# ESP32_Relay_Card_Relay.net
KiCad netlist of a schematic drawn in Altium Designer
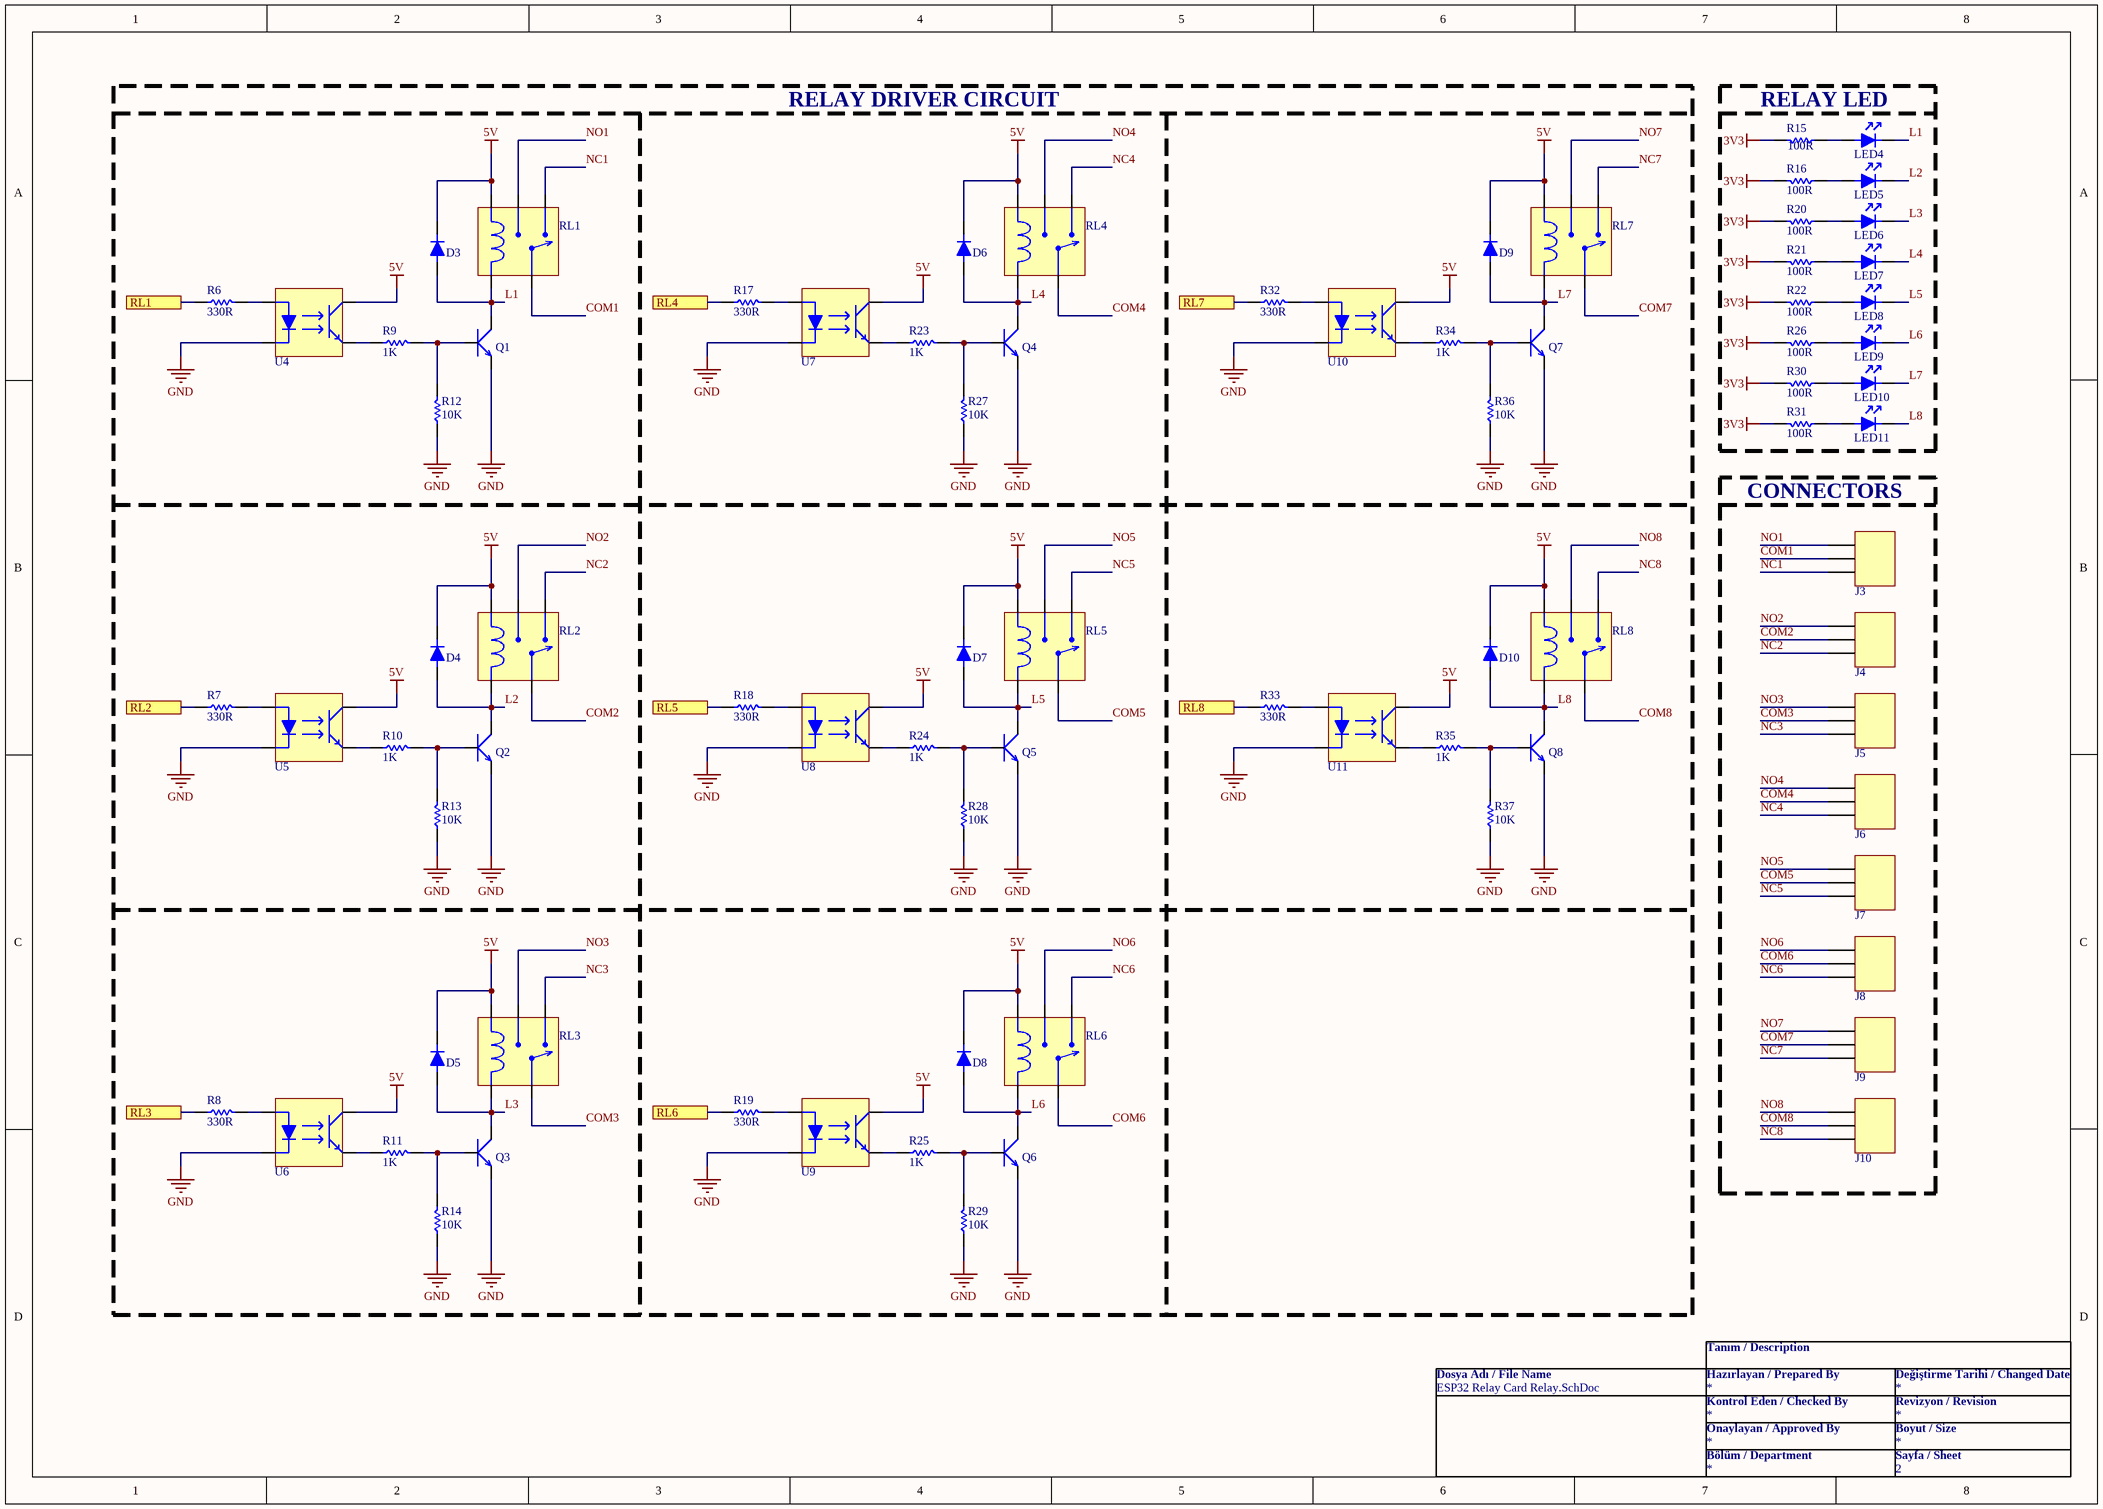
[diagram p0: ESP32 Relay Card Relay.SchDoc]

(export (version "E")
  (design (tool "Eeschema 10.0.6"))
  (components
    (comp (ref "D3")
      (value "1N5819W")
      (footprint "SOD-123F")
      (description "DIODE SCHOTTKY 40V 1A SOD-123F")
      (libsource (lib "ESP32 Relay Card") (part "SCHOTTKY DIODE SMD"))
    )
    (comp (ref "D4")
      (value "1N5819W")
      (footprint "SOD-123F")
      (description "DIODE SCHOTTKY 40V 1A SOD-123F")
      (libsource (lib "ESP32 Relay Card") (part "SCHOTTKY DIODE SMD"))
    )
    (comp (ref "D5")
      (value "1N5819W")
      (footprint "SOD-123F")
      (description "DIODE SCHOTTKY 40V 1A SOD-123F")
      (libsource (lib "ESP32 Relay Card") (part "SCHOTTKY DIODE SMD"))
    )
    (comp (ref "D6")
      (value "1N5819W")
      (footprint "SOD-123F")
      (description "DIODE SCHOTTKY 40V 1A SOD-123F")
      (libsource (lib "ESP32 Relay Card") (part "SCHOTTKY DIODE SMD"))
    )
    (comp (ref "D7")
      (value "1N5819W")
      (footprint "SOD-123F")
      (description "DIODE SCHOTTKY 40V 1A SOD-123F")
      (libsource (lib "ESP32 Relay Card") (part "SCHOTTKY DIODE SMD"))
    )
    (comp (ref "D8")
      (value "1N5819W")
      (footprint "SOD-123F")
      (description "DIODE SCHOTTKY 40V 1A SOD-123F")
      (libsource (lib "ESP32 Relay Card") (part "SCHOTTKY DIODE SMD"))
    )
    (comp (ref "D9")
      (value "1N5819W")
      (footprint "SOD-123F")
      (description "DIODE SCHOTTKY 40V 1A SOD-123F")
      (libsource (lib "ESP32 Relay Card") (part "SCHOTTKY DIODE SMD"))
    )
    (comp (ref "D10")
      (value "1N5819W")
      (footprint "SOD-123F")
      (description "DIODE SCHOTTKY 40V 1A SOD-123F")
      (libsource (lib "ESP32 Relay Card") (part "SCHOTTKY DIODE SMD"))
    )
    (comp (ref "J3")
      (value "OSTTA034163")
      (footprint "3POS CONNECTOR")
      (description "TERM BLK 3P 5.08MM PCB")
      (libsource (lib "ESP32 Relay Card") (part "3POS CONNECTOR"))
    )
    (comp (ref "J4")
      (value "OSTTA034163")
      (footprint "3POS CONNECTOR")
      (description "TERM BLK 3P 5.08MM PCB")
      (libsource (lib "ESP32 Relay Card") (part "3POS CONNECTOR"))
    )
    (comp (ref "J5")
      (value "OSTTA034163")
      (footprint "3POS CONNECTOR")
      (description "TERM BLK 3P 5.08MM PCB")
      (libsource (lib "ESP32 Relay Card") (part "3POS CONNECTOR"))
    )
    (comp (ref "J6")
      (value "OSTTA034163")
      (footprint "3POS CONNECTOR")
      (description "TERM BLK 3P 5.08MM PCB")
      (libsource (lib "ESP32 Relay Card") (part "3POS CONNECTOR"))
    )
    (comp (ref "J7")
      (value "OSTTA034163")
      (footprint "3POS CONNECTOR")
      (description "TERM BLK 3P 5.08MM PCB")
      (libsource (lib "ESP32 Relay Card") (part "3POS CONNECTOR"))
    )
    (comp (ref "J8")
      (value "OSTTA034163")
      (footprint "3POS CONNECTOR")
      (description "TERM BLK 3P 5.08MM PCB")
      (libsource (lib "ESP32 Relay Card") (part "3POS CONNECTOR"))
    )
    (comp (ref "J9")
      (value "OSTTA034163")
      (footprint "3POS CONNECTOR")
      (description "TERM BLK 3P 5.08MM PCB")
      (libsource (lib "ESP32 Relay Card") (part "3POS CONNECTOR"))
    )
    (comp (ref "J10")
      (value "OSTTA034163")
      (footprint "3POS CONNECTOR")
      (description "TERM BLK 3P 5.08MM PCB")
      (libsource (lib "ESP32 Relay Card") (part "3POS CONNECTOR"))
    )
    (comp (ref "LED4")
      (value "150080VS75000")
      (footprint "LED 0805 SMD")
      (description "LED GREEN 0805 SMD")
      (libsource (lib "ESP32 Relay Card") (part "GREEN LED 0805 SMD"))
    )
    (comp (ref "LED5")
      (value "150080VS75000")
      (footprint "LED 0805 SMD")
      (description "LED GREEN 0805 SMD")
      (libsource (lib "ESP32 Relay Card") (part "GREEN LED 0805 SMD"))
    )
    (comp (ref "LED6")
      (value "150080VS75000")
      (footprint "LED 0805 SMD")
      (description "LED GREEN 0805 SMD")
      (libsource (lib "ESP32 Relay Card") (part "GREEN LED 0805 SMD"))
    )
    (comp (ref "LED7")
      (value "150080VS75000")
      (footprint "LED 0805 SMD")
      (description "LED GREEN 0805 SMD")
      (libsource (lib "ESP32 Relay Card") (part "GREEN LED 0805 SMD"))
    )
    (comp (ref "LED8")
      (value "150080VS75000")
      (footprint "LED 0805 SMD")
      (description "LED GREEN 0805 SMD")
      (libsource (lib "ESP32 Relay Card") (part "GREEN LED 0805 SMD"))
    )
    (comp (ref "LED9")
      (value "150080VS75000")
      (footprint "LED 0805 SMD")
      (description "LED GREEN 0805 SMD")
      (libsource (lib "ESP32 Relay Card") (part "GREEN LED 0805 SMD"))
    )
    (comp (ref "LED10")
      (value "150080VS75000")
      (footprint "LED 0805 SMD")
      (description "LED GREEN 0805 SMD")
      (libsource (lib "ESP32 Relay Card") (part "GREEN LED 0805 SMD"))
    )
    (comp (ref "LED11")
      (value "150080VS75000")
      (footprint "LED 0805 SMD")
      (description "LED GREEN 0805 SMD")
      (libsource (lib "ESP32 Relay Card") (part "GREEN LED 0805 SMD"))
    )
    (comp (ref "Q1")
      (value "MMBT3904-7-F")
      (footprint "SOT23-3")
      (description "TRANS NPN 40V 0.2A SOT23-3")
      (libsource (lib "ESP32 Relay Card") (part "NPN TRANSISTOR SMD"))
    )
    (comp (ref "Q2")
      (value "MMBT3904-7-F")
      (footprint "SOT23-3")
      (description "TRANS NPN 40V 0.2A SOT23-3")
      (libsource (lib "ESP32 Relay Card") (part "NPN TRANSISTOR SMD"))
    )
    (comp (ref "Q3")
      (value "MMBT3904-7-F")
      (footprint "SOT23-3")
      (description "TRANS NPN 40V 0.2A SOT23-3")
      (libsource (lib "ESP32 Relay Card") (part "NPN TRANSISTOR SMD"))
    )
    (comp (ref "Q4")
      (value "MMBT3904-7-F")
      (footprint "SOT23-3")
      (description "TRANS NPN 40V 0.2A SOT23-3")
      (libsource (lib "ESP32 Relay Card") (part "NPN TRANSISTOR SMD"))
    )
    (comp (ref "Q5")
      (value "MMBT3904-7-F")
      (footprint "SOT23-3")
      (description "TRANS NPN 40V 0.2A SOT23-3")
      (libsource (lib "ESP32 Relay Card") (part "NPN TRANSISTOR SMD"))
    )
    (comp (ref "Q6")
      (value "MMBT3904-7-F")
      (footprint "SOT23-3")
      (description "TRANS NPN 40V 0.2A SOT23-3")
      (libsource (lib "ESP32 Relay Card") (part "NPN TRANSISTOR SMD"))
    )
    (comp (ref "Q7")
      (value "MMBT3904-7-F")
      (footprint "SOT23-3")
      (description "TRANS NPN 40V 0.2A SOT23-3")
      (libsource (lib "ESP32 Relay Card") (part "NPN TRANSISTOR SMD"))
    )
    (comp (ref "Q8")
      (value "MMBT3904-7-F")
      (footprint "SOT23-3")
      (description "TRANS NPN 40V 0.2A SOT23-3")
      (libsource (lib "ESP32 Relay Card") (part "NPN TRANSISTOR SMD"))
    )
    (comp (ref "R6")
      (value "330R")
      (footprint "RES 0603")
      (description "RES 330 OHM 1% 1/5W 0603")
      (fields (field (name "Comment") "CRGH0603F330R"))
      (libsource (lib "ESP32 Relay Card") (part "RES 330 OHM 0603 SMD"))
    )
    (comp (ref "R7")
      (value "330R")
      (footprint "RES 0603")
      (description "RES 330 OHM 1% 1/5W 0603")
      (fields (field (name "Comment") "CRGH0603F330R"))
      (libsource (lib "ESP32 Relay Card") (part "RES 330 OHM 0603 SMD"))
    )
    (comp (ref "R8")
      (value "330R")
      (footprint "RES 0603")
      (description "RES 330 OHM 1% 1/5W 0603")
      (fields (field (name "Comment") "CRGH0603F330R"))
      (libsource (lib "ESP32 Relay Card") (part "RES 330 OHM 0603 SMD"))
    )
    (comp (ref "R9")
      (value "1K")
      (footprint "RES 0603")
      (description "RES 1K OHM 5% 1/5W 0603")
      (fields (field (name "Comment") "CRGH0603J1K0"))
      (libsource (lib "ESP32 Relay Card") (part "RES 1K OHM 0603 SMD"))
    )
    (comp (ref "R10")
      (value "1K")
      (footprint "RES 0603")
      (description "RES 1K OHM 5% 1/5W 0603")
      (fields (field (name "Comment") "CRGH0603J1K0"))
      (libsource (lib "ESP32 Relay Card") (part "RES 1K OHM 0603 SMD"))
    )
    (comp (ref "R11")
      (value "1K")
      (footprint "RES 0603")
      (description "RES 1K OHM 5% 1/5W 0603")
      (fields (field (name "Comment") "CRGH0603J1K0"))
      (libsource (lib "ESP32 Relay Card") (part "RES 1K OHM 0603 SMD"))
    )
    (comp (ref "R12")
      (value "10K")
      (footprint "RES 0603")
      (description "RES 10K OHM 5% 1/5W 0603")
      (fields (field (name "Comment") "CRGH0603J10K"))
      (libsource (lib "ESP32 Relay Card") (part "RES 10K OHM 0603 SMD"))
    )
    (comp (ref "R13")
      (value "10K")
      (footprint "RES 0603")
      (description "RES 10K OHM 5% 1/5W 0603")
      (fields (field (name "Comment") "CRGH0603J10K"))
      (libsource (lib "ESP32 Relay Card") (part "RES 10K OHM 0603 SMD"))
    )
    (comp (ref "R14")
      (value "10K")
      (footprint "RES 0603")
      (description "RES 10K OHM 5% 1/5W 0603")
      (fields (field (name "Comment") "CRGH0603J10K"))
      (libsource (lib "ESP32 Relay Card") (part "RES 10K OHM 0603 SMD"))
    )
    (comp (ref "R15")
      (value "100R")
      (footprint "RES 0603")
      (description "RES 100 OHM 5% 1/5W 0603")
      (fields (field (name "Comment") "CRGH0603J100R"))
      (libsource (lib "ESP32 Relay Card") (part "RES 100 OHM 0603 SMD"))
    )
    (comp (ref "R16")
      (value "100R")
      (footprint "RES 0603")
      (description "RES 100 OHM 5% 1/5W 0603")
      (fields (field (name "Comment") "CRGH0603J100R"))
      (libsource (lib "ESP32 Relay Card") (part "RES 100 OHM 0603 SMD"))
    )
    (comp (ref "R17")
      (value "330R")
      (footprint "RES 0603")
      (description "RES 330 OHM 1% 1/5W 0603")
      (fields (field (name "Comment") "CRGH0603F330R"))
      (libsource (lib "ESP32 Relay Card") (part "RES 330 OHM 0603 SMD"))
    )
    (comp (ref "R18")
      (value "330R")
      (footprint "RES 0603")
      (description "RES 330 OHM 1% 1/5W 0603")
      (fields (field (name "Comment") "CRGH0603F330R"))
      (libsource (lib "ESP32 Relay Card") (part "RES 330 OHM 0603 SMD"))
    )
    (comp (ref "R19")
      (value "330R")
      (footprint "RES 0603")
      (description "RES 330 OHM 1% 1/5W 0603")
      (fields (field (name "Comment") "CRGH0603F330R"))
      (libsource (lib "ESP32 Relay Card") (part "RES 330 OHM 0603 SMD"))
    )
    (comp (ref "R20")
      (value "100R")
      (footprint "RES 0603")
      (description "RES 100 OHM 5% 1/5W 0603")
      (fields (field (name "Comment") "CRGH0603J100R"))
      (libsource (lib "ESP32 Relay Card") (part "RES 100 OHM 0603 SMD"))
    )
    (comp (ref "R21")
      (value "100R")
      (footprint "RES 0603")
      (description "RES 100 OHM 5% 1/5W 0603")
      (fields (field (name "Comment") "CRGH0603J100R"))
      (libsource (lib "ESP32 Relay Card") (part "RES 100 OHM 0603 SMD"))
    )
    (comp (ref "R22")
      (value "100R")
      (footprint "RES 0603")
      (description "RES 100 OHM 5% 1/5W 0603")
      (fields (field (name "Comment") "CRGH0603J100R"))
      (libsource (lib "ESP32 Relay Card") (part "RES 100 OHM 0603 SMD"))
    )
    (comp (ref "R23")
      (value "1K")
      (footprint "RES 0603")
      (description "RES 1K OHM 5% 1/5W 0603")
      (fields (field (name "Comment") "CRGH0603J1K0"))
      (libsource (lib "ESP32 Relay Card") (part "RES 1K OHM 0603 SMD"))
    )
    (comp (ref "R24")
      (value "1K")
      (footprint "RES 0603")
      (description "RES 1K OHM 5% 1/5W 0603")
      (fields (field (name "Comment") "CRGH0603J1K0"))
      (libsource (lib "ESP32 Relay Card") (part "RES 1K OHM 0603 SMD"))
    )
    (comp (ref "R25")
      (value "1K")
      (footprint "RES 0603")
      (description "RES 1K OHM 5% 1/5W 0603")
      (fields (field (name "Comment") "CRGH0603J1K0"))
      (libsource (lib "ESP32 Relay Card") (part "RES 1K OHM 0603 SMD"))
    )
    (comp (ref "R26")
      (value "100R")
      (footprint "RES 0603")
      (description "RES 100 OHM 5% 1/5W 0603")
      (fields (field (name "Comment") "CRGH0603J100R"))
      (libsource (lib "ESP32 Relay Card") (part "RES 100 OHM 0603 SMD"))
    )
    (comp (ref "R27")
      (value "10K")
      (footprint "RES 0603")
      (description "RES 10K OHM 5% 1/5W 0603")
      (fields (field (name "Comment") "CRGH0603J10K"))
      (libsource (lib "ESP32 Relay Card") (part "RES 10K OHM 0603 SMD"))
    )
    (comp (ref "R28")
      (value "10K")
      (footprint "RES 0603")
      (description "RES 10K OHM 5% 1/5W 0603")
      (fields (field (name "Comment") "CRGH0603J10K"))
      (libsource (lib "ESP32 Relay Card") (part "RES 10K OHM 0603 SMD"))
    )
    (comp (ref "R29")
      (value "10K")
      (footprint "RES 0603")
      (description "RES 10K OHM 5% 1/5W 0603")
      (fields (field (name "Comment") "CRGH0603J10K"))
      (libsource (lib "ESP32 Relay Card") (part "RES 10K OHM 0603 SMD"))
    )
    (comp (ref "R30")
      (value "100R")
      (footprint "RES 0603")
      (description "RES 100 OHM 5% 1/5W 0603")
      (fields (field (name "Comment") "CRGH0603J100R"))
      (libsource (lib "ESP32 Relay Card") (part "RES 100 OHM 0603 SMD"))
    )
    (comp (ref "R31")
      (value "100R")
      (footprint "RES 0603")
      (description "RES 100 OHM 5% 1/5W 0603")
      (fields (field (name "Comment") "CRGH0603J100R"))
      (libsource (lib "ESP32 Relay Card") (part "RES 100 OHM 0603 SMD"))
    )
    (comp (ref "R32")
      (value "330R")
      (footprint "RES 0603")
      (description "RES 330 OHM 1% 1/5W 0603")
      (fields (field (name "Comment") "CRGH0603F330R"))
      (libsource (lib "ESP32 Relay Card") (part "RES 330 OHM 0603 SMD"))
    )
    (comp (ref "R33")
      (value "330R")
      (footprint "RES 0603")
      (description "RES 330 OHM 1% 1/5W 0603")
      (fields (field (name "Comment") "CRGH0603F330R"))
      (libsource (lib "ESP32 Relay Card") (part "RES 330 OHM 0603 SMD"))
    )
    (comp (ref "R34")
      (value "1K")
      (footprint "RES 0603")
      (description "RES 1K OHM 5% 1/5W 0603")
      (fields (field (name "Comment") "CRGH0603J1K0"))
      (libsource (lib "ESP32 Relay Card") (part "RES 1K OHM 0603 SMD"))
    )
    (comp (ref "R35")
      (value "1K")
      (footprint "RES 0603")
      (description "RES 1K OHM 5% 1/5W 0603")
      (fields (field (name "Comment") "CRGH0603J1K0"))
      (libsource (lib "ESP32 Relay Card") (part "RES 1K OHM 0603 SMD"))
    )
    (comp (ref "R36")
      (value "10K")
      (footprint "RES 0603")
      (description "RES 10K OHM 5% 1/5W 0603")
      (fields (field (name "Comment") "CRGH0603J10K"))
      (libsource (lib "ESP32 Relay Card") (part "RES 10K OHM 0603 SMD"))
    )
    (comp (ref "R37")
      (value "10K")
      (footprint "RES 0603")
      (description "RES 10K OHM 5% 1/5W 0603")
      (fields (field (name "Comment") "CRGH0603J10K"))
      (libsource (lib "ESP32 Relay Card") (part "RES 10K OHM 0603 SMD"))
    )
    (comp (ref "RL1")
      (value "G5LE-1 DC5")
      (footprint "RELAY")
      (description "RELAY 5VDC COIL 10A")
      (libsource (lib "ESP32 Relay Card") (part "RELAY TH"))
    )
    (comp (ref "RL2")
      (value "G5LE-1 DC5")
      (footprint "RELAY")
      (description "RELAY 5VDC COIL 10A")
      (libsource (lib "ESP32 Relay Card") (part "RELAY TH"))
    )
    (comp (ref "RL3")
      (value "G5LE-1 DC5")
      (footprint "RELAY")
      (description "RELAY 5VDC COIL 10A")
      (libsource (lib "ESP32 Relay Card") (part "RELAY TH"))
    )
    (comp (ref "RL4")
      (value "G5LE-1 DC5")
      (footprint "RELAY")
      (description "RELAY 5VDC COIL 10A")
      (libsource (lib "ESP32 Relay Card") (part "RELAY TH"))
    )
    (comp (ref "RL5")
      (value "G5LE-1 DC5")
      (footprint "RELAY")
      (description "RELAY 5VDC COIL 10A")
      (libsource (lib "ESP32 Relay Card") (part "RELAY TH"))
    )
    (comp (ref "RL6")
      (value "G5LE-1 DC5")
      (footprint "RELAY")
      (description "RELAY 5VDC COIL 10A")
      (libsource (lib "ESP32 Relay Card") (part "RELAY TH"))
    )
    (comp (ref "RL7")
      (value "G5LE-1 DC5")
      (footprint "RELAY")
      (description "RELAY 5VDC COIL 10A")
      (libsource (lib "ESP32 Relay Card") (part "RELAY TH"))
    )
    (comp (ref "RL8")
      (value "G5LE-1 DC5")
      (footprint "RELAY")
      (description "RELAY 5VDC COIL 10A")
      (libsource (lib "ESP32 Relay Card") (part "RELAY TH"))
    )
    (comp (ref "U4")
      (value "APC-817B1-SL")
      (footprint "OPTOISOLATOR")
      (description "OPTOISOLATOR 5KV 1CH SMD")
      (libsource (lib "ESP32 Relay Card") (part "OPTOCOUPLER SMD"))
    )
    (comp (ref "U5")
      (value "APC-817B1-SL")
      (footprint "OPTOISOLATOR")
      (description "OPTOISOLATOR 5KV 1CH SMD")
      (libsource (lib "ESP32 Relay Card") (part "OPTOCOUPLER SMD"))
    )
    (comp (ref "U6")
      (value "APC-817B1-SL")
      (footprint "OPTOISOLATOR")
      (description "OPTOISOLATOR 5KV 1CH SMD")
      (libsource (lib "ESP32 Relay Card") (part "OPTOCOUPLER SMD"))
    )
    (comp (ref "U7")
      (value "APC-817B1-SL")
      (footprint "OPTOISOLATOR")
      (description "OPTOISOLATOR 5KV 1CH SMD")
      (libsource (lib "ESP32 Relay Card") (part "OPTOCOUPLER SMD"))
    )
    (comp (ref "U8")
      (value "APC-817B1-SL")
      (footprint "OPTOISOLATOR")
      (description "OPTOISOLATOR 5KV 1CH SMD")
      (libsource (lib "ESP32 Relay Card") (part "OPTOCOUPLER SMD"))
    )
    (comp (ref "U9")
      (value "APC-817B1-SL")
      (footprint "OPTOISOLATOR")
      (description "OPTOISOLATOR 5KV 1CH SMD")
      (libsource (lib "ESP32 Relay Card") (part "OPTOCOUPLER SMD"))
    )
    (comp (ref "U10")
      (value "APC-817B1-SL")
      (footprint "OPTOISOLATOR")
      (description "OPTOISOLATOR 5KV 1CH SMD")
      (libsource (lib "ESP32 Relay Card") (part "OPTOCOUPLER SMD"))
    )
    (comp (ref "U11")
      (value "APC-817B1-SL")
      (footprint "OPTOISOLATOR")
      (description "OPTOISOLATOR 5KV 1CH SMD")
      (libsource (lib "ESP32 Relay Card") (part "OPTOCOUPLER SMD"))
    )
  )
  (nets
    (net (code "1") (name "/COM1") (class "Default")
      (node (ref "J3") (pin "2") (pintype "passive"))
      (node (ref "RL1") (pin "1") (pintype "passive"))
    )
    (net (code "2") (name "/COM2") (class "Default")
      (node (ref "J4") (pin "2") (pintype "passive"))
      (node (ref "RL2") (pin "1") (pintype "passive"))
    )
    (net (code "3") (name "/COM3") (class "Default")
      (node (ref "J5") (pin "2") (pintype "passive"))
      (node (ref "RL3") (pin "1") (pintype "passive"))
    )
    (net (code "4") (name "/COM4") (class "Default")
      (node (ref "J6") (pin "2") (pintype "passive"))
      (node (ref "RL4") (pin "1") (pintype "passive"))
    )
    (net (code "5") (name "/COM5") (class "Default")
      (node (ref "J7") (pin "2") (pintype "passive"))
      (node (ref "RL5") (pin "1") (pintype "passive"))
    )
    (net (code "6") (name "/COM6") (class "Default")
      (node (ref "J8") (pin "2") (pintype "passive"))
      (node (ref "RL6") (pin "1") (pintype "passive"))
    )
    (net (code "7") (name "/COM7") (class "Default")
      (node (ref "J9") (pin "2") (pintype "passive"))
      (node (ref "RL7") (pin "1") (pintype "passive"))
    )
    (net (code "8") (name "/COM8") (class "Default")
      (node (ref "J10") (pin "2") (pintype "passive"))
      (node (ref "RL8") (pin "1") (pintype "passive"))
    )
    (net (code "9") (name "/L1") (class "Default")
      (node (ref "D3") (pin "1") (pintype "passive"))
      (node (ref "LED4") (pin "2") (pintype "passive"))
      (node (ref "Q1") (pin "3") (pintype "passive"))
      (node (ref "RL1") (pin "5") (pintype "passive"))
    )
    (net (code "10") (name "/L2") (class "Default")
      (node (ref "D4") (pin "1") (pintype "passive"))
      (node (ref "LED5") (pin "2") (pintype "passive"))
      (node (ref "Q2") (pin "3") (pintype "passive"))
      (node (ref "RL2") (pin "5") (pintype "passive"))
    )
    (net (code "11") (name "/L3") (class "Default")
      (node (ref "D5") (pin "1") (pintype "passive"))
      (node (ref "LED6") (pin "2") (pintype "passive"))
      (node (ref "Q3") (pin "3") (pintype "passive"))
      (node (ref "RL3") (pin "5") (pintype "passive"))
    )
    (net (code "12") (name "/L4") (class "Default")
      (node (ref "D6") (pin "1") (pintype "passive"))
      (node (ref "LED7") (pin "2") (pintype "passive"))
      (node (ref "Q4") (pin "3") (pintype "passive"))
      (node (ref "RL4") (pin "5") (pintype "passive"))
    )
    (net (code "13") (name "/L5") (class "Default")
      (node (ref "D7") (pin "1") (pintype "passive"))
      (node (ref "LED8") (pin "2") (pintype "passive"))
      (node (ref "Q5") (pin "3") (pintype "passive"))
      (node (ref "RL5") (pin "5") (pintype "passive"))
    )
    (net (code "14") (name "/L6") (class "Default")
      (node (ref "D8") (pin "1") (pintype "passive"))
      (node (ref "LED9") (pin "2") (pintype "passive"))
      (node (ref "Q6") (pin "3") (pintype "passive"))
      (node (ref "RL6") (pin "5") (pintype "passive"))
    )
    (net (code "15") (name "/L7") (class "Default")
      (node (ref "D9") (pin "1") (pintype "passive"))
      (node (ref "LED10") (pin "2") (pintype "passive"))
      (node (ref "Q7") (pin "3") (pintype "passive"))
      (node (ref "RL7") (pin "5") (pintype "passive"))
    )
    (net (code "16") (name "/L8") (class "Default")
      (node (ref "D10") (pin "1") (pintype "passive"))
      (node (ref "LED11") (pin "2") (pintype "passive"))
      (node (ref "Q8") (pin "3") (pintype "passive"))
      (node (ref "RL8") (pin "5") (pintype "passive"))
    )
    (net (code "17") (name "/NC1") (class "Default")
      (node (ref "J3") (pin "3") (pintype "passive"))
      (node (ref "RL1") (pin "4") (pintype "passive"))
    )
    (net (code "18") (name "/NC2") (class "Default")
      (node (ref "J4") (pin "3") (pintype "passive"))
      (node (ref "RL2") (pin "4") (pintype "passive"))
    )
    (net (code "19") (name "/NC3") (class "Default")
      (node (ref "J5") (pin "3") (pintype "passive"))
      (node (ref "RL3") (pin "4") (pintype "passive"))
    )
    (net (code "20") (name "/NC4") (class "Default")
      (node (ref "J6") (pin "3") (pintype "passive"))
      (node (ref "RL4") (pin "4") (pintype "passive"))
    )
    (net (code "21") (name "/NC5") (class "Default")
      (node (ref "J7") (pin "3") (pintype "passive"))
      (node (ref "RL5") (pin "4") (pintype "passive"))
    )
    (net (code "22") (name "/NC6") (class "Default")
      (node (ref "J8") (pin "3") (pintype "passive"))
      (node (ref "RL6") (pin "4") (pintype "passive"))
    )
    (net (code "23") (name "/NC7") (class "Default")
      (node (ref "J9") (pin "3") (pintype "passive"))
      (node (ref "RL7") (pin "4") (pintype "passive"))
    )
    (net (code "24") (name "/NC8") (class "Default")
      (node (ref "J10") (pin "3") (pintype "passive"))
      (node (ref "RL8") (pin "4") (pintype "passive"))
    )
    (net (code "25") (name "/NO1") (class "Default")
      (node (ref "J3") (pin "1") (pintype "passive"))
      (node (ref "RL1") (pin "3") (pintype "passive"))
    )
    (net (code "26") (name "/NO2") (class "Default")
      (node (ref "J4") (pin "1") (pintype "passive"))
      (node (ref "RL2") (pin "3") (pintype "passive"))
    )
    (net (code "27") (name "/NO3") (class "Default")
      (node (ref "J5") (pin "1") (pintype "passive"))
      (node (ref "RL3") (pin "3") (pintype "passive"))
    )
    (net (code "28") (name "/NO4") (class "Default")
      (node (ref "J6") (pin "1") (pintype "passive"))
      (node (ref "RL4") (pin "3") (pintype "passive"))
    )
    (net (code "29") (name "/NO5") (class "Default")
      (node (ref "J7") (pin "1") (pintype "passive"))
      (node (ref "RL5") (pin "3") (pintype "passive"))
    )
    (net (code "30") (name "/NO6") (class "Default")
      (node (ref "J8") (pin "1") (pintype "passive"))
      (node (ref "RL6") (pin "3") (pintype "passive"))
    )
    (net (code "31") (name "/NO7") (class "Default")
      (node (ref "J9") (pin "1") (pintype "passive"))
      (node (ref "RL7") (pin "3") (pintype "passive"))
    )
    (net (code "32") (name "/NO8") (class "Default")
      (node (ref "J10") (pin "1") (pintype "passive"))
      (node (ref "RL8") (pin "3") (pintype "passive"))
    )
    (net (code "33") (name "/RL1") (class "Default")
      (node (ref "R6") (pin "1") (pinfunction "1_1") (pintype "passive"))
    )
    (net (code "34") (name "/RL2") (class "Default")
      (node (ref "R7") (pin "1") (pinfunction "1_1") (pintype "passive"))
    )
    (net (code "35") (name "/RL3") (class "Default")
      (node (ref "R8") (pin "1") (pinfunction "1_1") (pintype "passive"))
    )
    (net (code "36") (name "/RL4") (class "Default")
      (node (ref "R17") (pin "1") (pinfunction "1_1") (pintype "passive"))
    )
    (net (code "37") (name "/RL5") (class "Default")
      (node (ref "R18") (pin "1") (pinfunction "1_1") (pintype "passive"))
    )
    (net (code "38") (name "/RL6") (class "Default")
      (node (ref "R19") (pin "1") (pinfunction "1_1") (pintype "passive"))
    )
    (net (code "39") (name "/RL7") (class "Default")
      (node (ref "R32") (pin "1") (pinfunction "1_1") (pintype "passive"))
    )
    (net (code "40") (name "/RL8") (class "Default")
      (node (ref "R33") (pin "1") (pinfunction "1_1") (pintype "passive"))
    )
    (net (code "41") (name "3V3") (class "Default")
      (node (ref "R15") (pin "2") (pintype "passive"))
      (node (ref "R16") (pin "2") (pintype "passive"))
      (node (ref "R20") (pin "2") (pintype "passive"))
      (node (ref "R21") (pin "2") (pintype "passive"))
      (node (ref "R22") (pin "2") (pintype "passive"))
      (node (ref "R26") (pin "2") (pintype "passive"))
      (node (ref "R30") (pin "2") (pintype "passive"))
      (node (ref "R31") (pin "2") (pintype "passive"))
    )
    (net (code "42") (name "5V") (class "Default")
      (node (ref "D10") (pin "2") (pintype "passive"))
      (node (ref "D3") (pin "2") (pintype "passive"))
      (node (ref "D4") (pin "2") (pintype "passive"))
      (node (ref "D5") (pin "2") (pintype "passive"))
      (node (ref "D6") (pin "2") (pintype "passive"))
      (node (ref "D7") (pin "2") (pintype "passive"))
      (node (ref "D8") (pin "2") (pintype "passive"))
      (node (ref "D9") (pin "2") (pintype "passive"))
      (node (ref "RL1") (pin "2") (pintype "passive"))
      (node (ref "RL2") (pin "2") (pintype "passive"))
      (node (ref "RL3") (pin "2") (pintype "passive"))
      (node (ref "RL4") (pin "2") (pintype "passive"))
      (node (ref "RL5") (pin "2") (pintype "passive"))
      (node (ref "RL6") (pin "2") (pintype "passive"))
      (node (ref "RL7") (pin "2") (pintype "passive"))
      (node (ref "RL8") (pin "2") (pintype "passive"))
      (node (ref "U10") (pin "4") (pintype "passive"))
      (node (ref "U11") (pin "4") (pintype "passive"))
      (node (ref "U4") (pin "4") (pintype "passive"))
      (node (ref "U5") (pin "4") (pintype "passive"))
      (node (ref "U6") (pin "4") (pintype "passive"))
      (node (ref "U7") (pin "4") (pintype "passive"))
      (node (ref "U8") (pin "4") (pintype "passive"))
      (node (ref "U9") (pin "4") (pintype "passive"))
    )
    (net (code "43") (name "GND") (class "Default")
      (node (ref "Q1") (pin "2") (pintype "passive"))
      (node (ref "Q2") (pin "2") (pintype "passive"))
      (node (ref "Q3") (pin "2") (pintype "passive"))
      (node (ref "Q4") (pin "2") (pintype "passive"))
      (node (ref "Q5") (pin "2") (pintype "passive"))
      (node (ref "Q6") (pin "2") (pintype "passive"))
      (node (ref "Q7") (pin "2") (pintype "passive"))
      (node (ref "Q8") (pin "2") (pintype "passive"))
      (node (ref "R12") (pin "1") (pintype "passive"))
      (node (ref "R13") (pin "1") (pintype "passive"))
      (node (ref "R14") (pin "1") (pintype "passive"))
      (node (ref "R27") (pin "1") (pintype "passive"))
      (node (ref "R28") (pin "1") (pintype "passive"))
      (node (ref "R29") (pin "1") (pintype "passive"))
      (node (ref "R36") (pin "1") (pintype "passive"))
      (node (ref "R37") (pin "1") (pintype "passive"))
      (node (ref "U10") (pin "2") (pintype "passive"))
      (node (ref "U11") (pin "2") (pintype "passive"))
      (node (ref "U4") (pin "2") (pintype "passive"))
      (node (ref "U5") (pin "2") (pintype "passive"))
      (node (ref "U6") (pin "2") (pintype "passive"))
      (node (ref "U7") (pin "2") (pintype "passive"))
      (node (ref "U8") (pin "2") (pintype "passive"))
      (node (ref "U9") (pin "2") (pintype "passive"))
    )
    (net (code "44") (name "Net-(LED4-Pad1)") (class "Default")
      (node (ref "LED4") (pin "1") (pintype "passive"))
      (node (ref "R15") (pin "1") (pintype "passive"))
    )
    (net (code "45") (name "Net-(LED5-Pad1)") (class "Default")
      (node (ref "LED5") (pin "1") (pintype "passive"))
      (node (ref "R16") (pin "1") (pintype "passive"))
    )
    (net (code "46") (name "Net-(LED6-Pad1)") (class "Default")
      (node (ref "LED6") (pin "1") (pintype "passive"))
      (node (ref "R20") (pin "1") (pintype "passive"))
    )
    (net (code "47") (name "Net-(LED7-Pad1)") (class "Default")
      (node (ref "LED7") (pin "1") (pintype "passive"))
      (node (ref "R21") (pin "1") (pintype "passive"))
    )
    (net (code "48") (name "Net-(LED8-Pad1)") (class "Default")
      (node (ref "LED8") (pin "1") (pintype "passive"))
      (node (ref "R22") (pin "1") (pintype "passive"))
    )
    (net (code "49") (name "Net-(LED9-Pad1)") (class "Default")
      (node (ref "LED9") (pin "1") (pintype "passive"))
      (node (ref "R26") (pin "1") (pintype "passive"))
    )
    (net (code "50") (name "Net-(LED10-Pad1)") (class "Default")
      (node (ref "LED10") (pin "1") (pintype "passive"))
      (node (ref "R30") (pin "1") (pintype "passive"))
    )
    (net (code "51") (name "Net-(LED11-Pad1)") (class "Default")
      (node (ref "LED11") (pin "1") (pintype "passive"))
      (node (ref "R31") (pin "1") (pintype "passive"))
    )
    (net (code "52") (name "Net-(Q1-Pad1)") (class "Default")
      (node (ref "Q1") (pin "1") (pintype "passive"))
      (node (ref "R12") (pin "2") (pintype "passive"))
      (node (ref "R9") (pin "2") (pintype "passive"))
    )
    (net (code "53") (name "Net-(Q2-Pad1)") (class "Default")
      (node (ref "Q2") (pin "1") (pintype "passive"))
      (node (ref "R10") (pin "2") (pintype "passive"))
      (node (ref "R13") (pin "2") (pintype "passive"))
    )
    (net (code "54") (name "Net-(Q3-Pad1)") (class "Default")
      (node (ref "Q3") (pin "1") (pintype "passive"))
      (node (ref "R11") (pin "2") (pintype "passive"))
      (node (ref "R14") (pin "2") (pintype "passive"))
    )
    (net (code "55") (name "Net-(Q4-Pad1)") (class "Default")
      (node (ref "Q4") (pin "1") (pintype "passive"))
      (node (ref "R23") (pin "2") (pintype "passive"))
      (node (ref "R27") (pin "2") (pintype "passive"))
    )
    (net (code "56") (name "Net-(Q5-Pad1)") (class "Default")
      (node (ref "Q5") (pin "1") (pintype "passive"))
      (node (ref "R24") (pin "2") (pintype "passive"))
      (node (ref "R28") (pin "2") (pintype "passive"))
    )
    (net (code "57") (name "Net-(Q6-Pad1)") (class "Default")
      (node (ref "Q6") (pin "1") (pintype "passive"))
      (node (ref "R25") (pin "2") (pintype "passive"))
      (node (ref "R29") (pin "2") (pintype "passive"))
    )
    (net (code "58") (name "Net-(Q7-Pad1)") (class "Default")
      (node (ref "Q7") (pin "1") (pintype "passive"))
      (node (ref "R34") (pin "2") (pintype "passive"))
      (node (ref "R36") (pin "2") (pintype "passive"))
    )
    (net (code "59") (name "Net-(Q8-Pad1)") (class "Default")
      (node (ref "Q8") (pin "1") (pintype "passive"))
      (node (ref "R35") (pin "2") (pintype "passive"))
      (node (ref "R37") (pin "2") (pintype "passive"))
    )
    (net (code "60") (name "Net-(R6-Pad2)") (class "Default")
      (node (ref "R6") (pin "2") (pinfunction "2_2") (pintype "passive"))
      (node (ref "U4") (pin "1") (pintype "passive"))
    )
    (net (code "61") (name "Net-(R7-Pad2)") (class "Default")
      (node (ref "R7") (pin "2") (pinfunction "2_2") (pintype "passive"))
      (node (ref "U5") (pin "1") (pintype "passive"))
    )
    (net (code "62") (name "Net-(R8-Pad2)") (class "Default")
      (node (ref "R8") (pin "2") (pinfunction "2_2") (pintype "passive"))
      (node (ref "U6") (pin "1") (pintype "passive"))
    )
    (net (code "63") (name "Net-(R9-Pad1)") (class "Default")
      (node (ref "R9") (pin "1") (pintype "passive"))
      (node (ref "U4") (pin "3") (pintype "passive"))
    )
    (net (code "64") (name "Net-(R10-Pad1)") (class "Default")
      (node (ref "R10") (pin "1") (pintype "passive"))
      (node (ref "U5") (pin "3") (pintype "passive"))
    )
    (net (code "65") (name "Net-(R11-Pad1)") (class "Default")
      (node (ref "R11") (pin "1") (pintype "passive"))
      (node (ref "U6") (pin "3") (pintype "passive"))
    )
    (net (code "66") (name "Net-(R17-Pad2)") (class "Default")
      (node (ref "R17") (pin "2") (pinfunction "2_2") (pintype "passive"))
      (node (ref "U7") (pin "1") (pintype "passive"))
    )
    (net (code "67") (name "Net-(R18-Pad2)") (class "Default")
      (node (ref "R18") (pin "2") (pinfunction "2_2") (pintype "passive"))
      (node (ref "U8") (pin "1") (pintype "passive"))
    )
    (net (code "68") (name "Net-(R19-Pad2)") (class "Default")
      (node (ref "R19") (pin "2") (pinfunction "2_2") (pintype "passive"))
      (node (ref "U9") (pin "1") (pintype "passive"))
    )
    (net (code "69") (name "Net-(R23-Pad1)") (class "Default")
      (node (ref "R23") (pin "1") (pintype "passive"))
      (node (ref "U7") (pin "3") (pintype "passive"))
    )
    (net (code "70") (name "Net-(R24-Pad1)") (class "Default")
      (node (ref "R24") (pin "1") (pintype "passive"))
      (node (ref "U8") (pin "3") (pintype "passive"))
    )
    (net (code "71") (name "Net-(R25-Pad1)") (class "Default")
      (node (ref "R25") (pin "1") (pintype "passive"))
      (node (ref "U9") (pin "3") (pintype "passive"))
    )
    (net (code "72") (name "Net-(R32-Pad2)") (class "Default")
      (node (ref "R32") (pin "2") (pinfunction "2_2") (pintype "passive"))
      (node (ref "U10") (pin "1") (pintype "passive"))
    )
    (net (code "73") (name "Net-(R33-Pad2)") (class "Default")
      (node (ref "R33") (pin "2") (pinfunction "2_2") (pintype "passive"))
      (node (ref "U11") (pin "1") (pintype "passive"))
    )
    (net (code "74") (name "Net-(R34-Pad1)") (class "Default")
      (node (ref "R34") (pin "1") (pintype "passive"))
      (node (ref "U10") (pin "3") (pintype "passive"))
    )
    (net (code "75") (name "Net-(R35-Pad1)") (class "Default")
      (node (ref "R35") (pin "1") (pintype "passive"))
      (node (ref "U11") (pin "3") (pintype "passive"))
    )
  )
)
